# QR_Scanning2_V1_STM32.net
KiCad netlist of a schematic drawn in Altium Designer
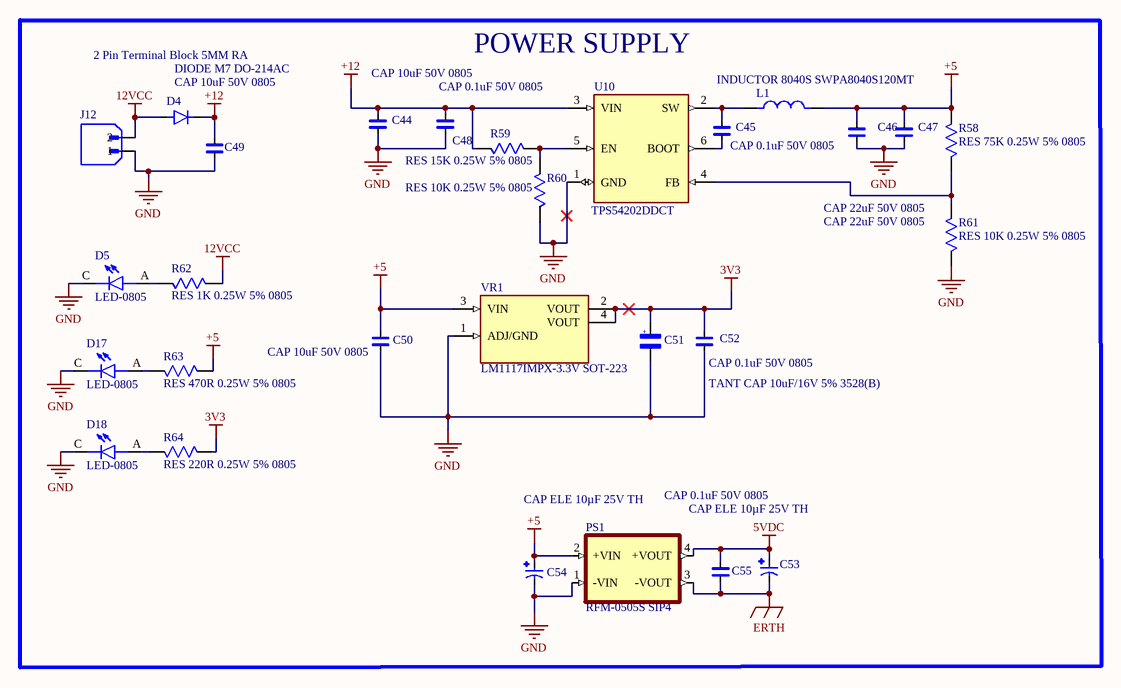
[diagram p0: QR_Scanning2_V1_STM32.SchDoc]

(export (version "E")
  (design (tool "Eeschema 10.0.6"))
  (components
    (comp (ref "C44")
      (value "CAP 10uF 50V 0805")
      (footprint "CAP CER 0.1uF/50V 5%")
      (description "CAP CER 0.1uF/50V  Ceramic Capacitor X7R 0805 (2012 Metric) SMT")
      (fields (field (name "MF") "Samsung") (field (name "MP") "CL21B104KCFNNNE"))
      (libsource (lib "GENERAL_ARDUINO+ESP32_PCB") (part "CAP CER 0.1uF/50V 5%"))
    )
    (comp (ref "C45")
      (value "CAP 0.1uF 50V 0805")
      (footprint "CAP CER 0.1uF/50V 5%")
      (description "CAP CER 0.1uF/50V  Ceramic Capacitor X7R 0805 (2012 Metric) SMT")
      (fields (field (name "MF") "Samsung") (field (name "MP") "CL21B104KCFNNNE"))
      (libsource (lib "GENERAL_ARDUINO+ESP32_PCB") (part "CAP CER 0.1uF/50V 5%"))
    )
    (comp (ref "C46")
      (value "CAP 22uF 50V 0805")
      (footprint "CAP CER 0.1uF/50V 5%")
      (description "CAP CER 0.1uF/50V  Ceramic Capacitor X7R 0805 (2012 Metric) SMT")
      (fields (field (name "MF") "Samsung") (field (name "MP") "CL21B104KCFNNNE"))
      (libsource (lib "GENERAL_ARDUINO+ESP32_PCB") (part "CAP CER 0.1uF/50V 5%"))
    )
    (comp (ref "C47")
      (value "CAP 22uF 50V 0805")
      (footprint "CAP CER 0.1uF/50V 5%")
      (description "CAP CER 0.1uF/50V  Ceramic Capacitor X7R 0805 (2012 Metric) SMT")
      (fields (field (name "MF") "Samsung") (field (name "MP") "CL21B104KCFNNNE"))
      (libsource (lib "GENERAL_ARDUINO+ESP32_PCB") (part "CAP CER 0.1uF/50V 5%"))
    )
    (comp (ref "C48")
      (value "CAP 0.1uF 50V 0805")
      (footprint "CAP CER 0.1uF/50V 5%")
      (description "CAP CER 0.1uF/50V  Ceramic Capacitor X7R 0805 (2012 Metric) SMT")
      (fields (field (name "MF") "Samsung") (field (name "MP") "CL21B104KCFNNNE"))
      (libsource (lib "GENERAL_ARDUINO+ESP32_PCB") (part "CAP CER 0.1uF/50V 5%"))
    )
    (comp (ref "C49")
      (value "CAP 10uF 50V 0805")
      (footprint "CAP CER 0.1uF/50V 5%")
      (description "CAP CER 0.1uF/50V  Ceramic Capacitor X7R 0805 (2012 Metric) SMT")
      (fields (field (name "MF") "Samsung") (field (name "MP") "CL21B104KCFNNNE"))
      (libsource (lib "Ticket Scanning") (part "CAP CER 0.1uF/50V 5%"))
    )
    (comp (ref "C50")
      (value "CAP 10uF 50V 0805")
      (footprint "CAP CER 0.1uF/50V 5%")
      (description "CAP CER 0.1uF/50V  Ceramic Capacitor X7R 0805 (2012 Metric) SMT")
      (fields (field (name "MF") "Samsung") (field (name "MP") "CL21B104KCFNNNE"))
      (libsource (lib "Ticket Scanning") (part "CAP CER 0.1uF/50V 5%"))
    )
    (comp (ref "C51")
      (value "TANT CAP 10uF/16V 5% 3528(B)")
      (footprint "TANT CAP 3528(B)")
      (description "10 ÂµF Molded Tantalum Polymer Capacitor 25 V 1411 (3528 Metric), 1210 150mOhm TCJB106M025R0150")
      (fields (field (name "MF") "AVX") (field (name "MP") "TCJB106M025R0150"))
      (libsource (lib "Ticket Scanning") (part "TANT CAP 10uF/16V 5% 3528(B)"))
    )
    (comp (ref "C52")
      (value "CAP 0.1uF 50V 0805")
      (footprint "CAP CER 0.1uF/50V 5%")
      (description "CAP CER 0.1uF/50V  Ceramic Capacitor X7R 0805 (2012 Metric) SMT")
      (fields (field (name "MF") "Samsung") (field (name "MP") "CL21B104KCFNNNE"))
      (libsource (lib "Ticket Scanning") (part "CAP CER 0.1uF/50V 5%"))
    )
    (comp (ref "C53")
      (value "CAP ELE 10µF 25V TH")
      (footprint "CAP ELE 10µF 25V TH")
      (description "10µF 25V Aluminum Electrolytic Capacitors Radial Lead Type TH, Dia-5mm, Pitch-2mm ECEA1EN100UI")
      (fields (field (name "MF") "Panasonic") (field (name "DIGI-KEY_PART_NUMBER") "ECE-A1EN100UI-ND"))
      (libsource (lib "PGS") (part "CAP ELE 10µF 25V TH"))
    )
    (comp (ref "C54")
      (value "CAP ELE 10µF 25V TH")
      (footprint "CAP ELE 10µF 25V TH")
      (description "10µF 25V Aluminum Electrolytic Capacitors Radial Lead Type TH, Dia-5mm, Pitch-2mm ECEA1EN100UI")
      (fields (field (name "MF") "Panasonic") (field (name "DIGI-KEY_PART_NUMBER") "ECE-A1EN100UI-ND"))
      (libsource (lib "PGS") (part "CAP ELE 10µF 25V TH"))
    )
    (comp (ref "C55")
      (value "CAP 0.1uF 50V 0805")
      (footprint "CAP CER 0.1uF/50V 5%")
      (description "CAP CER 0.1uF/50V  Ceramic Capacitor X7R 0805 (2012 Metric)")
      (fields (field (name "MF") "Samsung") (field (name "MP") "CL21B104KCFNNNE"))
      (libsource (lib "PGS") (part "CAP CER 0.1uF/50V 5%"))
    )
    (comp (ref "D4")
      (value "DIODE M7 DO-214AC")
      (footprint "DIODE M7 DO-214AC")
      (description "M7 General Purpose SMD Rectifier Diode SMA (DO-214AC) 1A 1000V 1n4007 RS2MA")
      (fields (field (name "MF") "Taiwan Semiconductor") (field (name "MP") "RS2MA"))
      (libsource (lib "QR_Scanning_STM32") (part "DIODE M7 DO-214AC"))
    )
    (comp (ref "D5")
      (value "LED-0805")
      (footprint "LED-0805")
      (description "Red 640nm LED Indication - Discrete 1.85V 0805 (2012 Metric) APT2012SRCPRV")
      (fields (field (name "MF") "Kingbright") (field (name "MP") "APT2012SRCPRV"))
      (libsource (lib "P10_ESP32") (part "LED-0805"))
    )
    (comp (ref "D17")
      (value "LED-0805")
      (footprint "LED-0805")
      (description "Red 640nm LED Indication - Discrete 1.85V 0805 (2012 Metric) APT2012SRCPRV")
      (fields (field (name "MF") "Kingbright") (field (name "MP") "APT2012SRCPRV"))
      (libsource (lib "P10_ESP32") (part "LED-0805"))
    )
    (comp (ref "D18")
      (value "LED-0805")
      (footprint "LED-0805")
      (description "Red 640nm LED Indication - Discrete 1.85V 0805 (2012 Metric) APT2012SRCPRV")
      (fields (field (name "MF") "Kingbright") (field (name "MP") "APT2012SRCPRV"))
      (libsource (lib "P10_ESP32") (part "LED-0805"))
    )
    (comp (ref "J12")
      (value "2 Pin Terminal Block 5MM RA")
      (footprint "2 Pin Terminal Block 5MM RA")
      (description "2 Pin Terminal Block HDR 5MM THT RA _OQ0271510000G")
      (fields (field (name "MF") "Amphenol Anytek") (field (name "MP") "OQ0271510000G"))
      (libsource (lib "Ticket Scanning") (part "2 Pin Terminal Block 5MM RA"))
    )
    (comp (ref "L1")
      (value "INDUCTOR 8040S SWPA8040S120MT")
      (footprint "INDUCTOR 8040S SWPA8040S120MT")
      (description "SWPA8040S120MT SMD 8.0×8.0x4.0mm 8040S 12uH Â±20% 2.8A 142 mOhm SMT Shielded Wirewound Inductor")
      (fields (field (name "MF") "Abracon LLC") (field (name "MP") "ASPI-8040S-510M-T"))
      (libsource (lib "QR_Scanning_STM32") (part "INDUCTOR 8040S SWPA8040S120MT"))
    )
    (comp (ref "PS1")
      (value "RFM-0505S SIP4")
      (footprint "RFM-0505S")
      (fields (field (name "MF") "Recom Power") (field (name "MP") "RFM-0505S"))
      (libsource (lib "PGS") (part "RFM-0505S"))
    )
    (comp (ref "R58")
      (value "RES 75K 0.25W 5% 0805")
      (footprint "RES 0805 10K/0.25W 5%")
      (description "RESISTOR, THICK FILM, 10K, 5%, 0805 0.25W SMT")
      (fields (field (name "MP") "ERJ-6GEYJ103V") (field (name "MF") "Panasonic Electronic"))
      (libsource (lib "GENERAL_ARDUINO+ESP32_PCB") (part "RES 10K 0.25W 5% 0805"))
    )
    (comp (ref "R59")
      (value "RES 15K 0.25W 5% 0805")
      (footprint "RES 0805 10K/0.25W 5%")
      (description "RESISTOR, THICK FILM, 10K, 5%, 0805 0.25W SMT")
      (fields (field (name "MP") "ERJ-6GEYJ103V") (field (name "MF") "Panasonic Electronic"))
      (libsource (lib "GENERAL_ARDUINO+ESP32_PCB") (part "RES 10K 0.25W 5% 0805"))
    )
    (comp (ref "R60")
      (value "RES 10K 0.25W 5% 0805")
      (footprint "RES 0805 10K/0.25W 5%")
      (description "RESISTOR, THICK FILM, 10K, 5%, 0805 0.25W SMT")
      (fields (field (name "MP") "ERJ-6GEYJ103V") (field (name "MF") "Panasonic Electronic"))
      (libsource (lib "GENERAL_ARDUINO+ESP32_PCB") (part "RES 10K 0.25W 5% 0805"))
    )
    (comp (ref "R61")
      (value "RES 10K 0.25W 5% 0805")
      (footprint "RES 0805 10K/0.25W 5%")
      (description "RESISTOR, THICK FILM, 10K, 5%, 0805 0.25W SMT")
      (fields (field (name "MP") "ERJ-6GEYJ103V") (field (name "MF") "Panasonic Electronic"))
      (libsource (lib "GENERAL_ARDUINO+ESP32_PCB") (part "RES 10K 0.25W 5% 0805"))
    )
    (comp (ref "R62")
      (value "RES 1K 0.25W 5% 0805")
      (footprint "RES 0805 10K/0.25W 5%")
      (description "RESISTOR, THICK FILM, 10K, 5%, 0805 0.25W SMT")
      (fields (field (name "MP") "ERJ-6GEYJ103V") (field (name "MF") "Panasonic Electronic"))
      (libsource (lib "Ticket Scanning") (part "RES 10K 0.25W 5% 0805"))
    )
    (comp (ref "R63")
      (value "RES 470R 0.25W 5% 0805")
      (footprint "RES 0805 10K/0.25W 5%")
      (description "RESISTOR, THICK FILM, 10K, 5%, 0805 0.25W SMT")
      (fields (field (name "MP") "ERJ-6GEYJ103V") (field (name "MF") "Panasonic Electronic"))
      (libsource (lib "Ticket Scanning") (part "RES 10K 0.25W 5% 0805"))
    )
    (comp (ref "R64")
      (value "RES 220R 0.25W 5% 0805")
      (footprint "RES 0805 10K/0.25W 5%")
      (description "RESISTOR, THICK FILM, 10K, 5%, 0805 0.25W SMT")
      (fields (field (name "MP") "ERJ-6GEYJ103V") (field (name "MF") "Panasonic Electronic"))
      (libsource (lib "Ticket Scanning") (part "RES 10K 0.25W 5% 0805"))
    )
    (comp (ref "U10")
      (value "TPS54202DDCT")
      (footprint "TPS54202DDCT")
      (description "4.5V to 28V Input, 2A Output, EMI Friendly Synchronous Step-Down Converter SOT23-6")
      (fields (field (name "MF") "Texas Instruments"))
      (libsource (lib "GENERAL_ARDUINO+ESP32_PCB") (part "TPS54202DDCT"))
    )
    (comp (ref "VR1")
      (value "LM1117IMPX-3.3V SOT-223")
      (footprint "LM1117IMPX-3.3V SOT-223")
      (description "LM1117IMPX-3.3V 800-mA 15-V linear voltage regulator SOT-223")
      (fields (field (name "MF") "Texas Instruments") (field (name "MP") "LM1117IMPX-5.0/NOPB"))
      (libsource (lib "Ticket Scanning") (part "LM1117IMPX-3.3V SOT-223"))
    )
  )
  (nets
    (net (code "1") (name "+5") (class "Default")
      (node (ref "C46") (pin "2") (pinfunction "2_2") (pintype "passive"))
      (node (ref "C47") (pin "2") (pinfunction "2_2") (pintype "passive"))
      (node (ref "C50") (pin "2") (pinfunction "2_2") (pintype "passive"))
      (node (ref "C54") (pin "P") (pinfunction "P_P") (pintype "passive"))
      (node (ref "L1") (pin "2") (pinfunction "2_2") (pintype "passive"))
      (node (ref "PS1") (pin "2") (pinfunction "+VIN_2") (pintype "input"))
      (node (ref "R58") (pin "2") (pinfunction "2_2") (pintype "passive"))
      (node (ref "R63") (pin "2") (pinfunction "2_2") (pintype "passive"))
      (node (ref "VR1") (pin "3") (pinfunction "VIN_3") (pintype "input"))
    )
    (net (code "2") (name "+12") (class "Default")
      (node (ref "C44") (pin "2") (pinfunction "2_2") (pintype "passive"))
      (node (ref "C48") (pin "2") (pinfunction "2_2") (pintype "passive"))
      (node (ref "C49") (pin "2") (pinfunction "2_2") (pintype "passive"))
      (node (ref "D4") (pin "C") (pinfunction "K_C") (pintype "passive"))
      (node (ref "R59") (pin "1") (pinfunction "1_1") (pintype "passive"))
      (node (ref "U10") (pin "3") (pinfunction "VIN_3") (pintype "input"))
    )
    (net (code "3") (name "3V3") (class "Default")
      (node (ref "C51") (pin "1") (pinfunction "1_1") (pintype "passive"))
      (node (ref "C52") (pin "2") (pinfunction "2_2") (pintype "passive"))
      (node (ref "R64") (pin "2") (pinfunction "2_2") (pintype "passive"))
      (node (ref "VR1") (pin "2") (pinfunction "VOUT_2") (pintype "power_in"))
      (node (ref "VR1") (pin "4") (pinfunction "VOUT_4") (pintype "power_in"))
    )
    (net (code "4") (name "5VDC") (class "Default")
      (node (ref "C53") (pin "P") (pinfunction "P_P") (pintype "passive"))
      (node (ref "C55") (pin "2") (pinfunction "2_2") (pintype "passive"))
      (node (ref "PS1") (pin "4") (pinfunction "+VOUT_4") (pintype "output"))
    )
    (net (code "5") (name "12VCC") (class "Default")
      (node (ref "D4") (pin "A") (pinfunction "A_A") (pintype "passive"))
      (node (ref "J12") (pin "2") (pinfunction "2_2") (pintype "passive"))
      (node (ref "R62") (pin "2") (pinfunction "2_2") (pintype "passive"))
    )
    (net (code "6") (name "ERTH") (class "Default")
      (node (ref "C53") (pin "N") (pinfunction "N_N") (pintype "passive"))
      (node (ref "C55") (pin "1") (pinfunction "1_1") (pintype "passive"))
      (node (ref "PS1") (pin "3") (pinfunction "-VOUT_3") (pintype "output"))
    )
    (net (code "7") (name "GND") (class "Default")
      (node (ref "C44") (pin "1") (pinfunction "1_1") (pintype "passive"))
      (node (ref "C46") (pin "1") (pinfunction "1_1") (pintype "passive"))
      (node (ref "C47") (pin "1") (pinfunction "1_1") (pintype "passive"))
      (node (ref "C48") (pin "1") (pinfunction "1_1") (pintype "passive"))
      (node (ref "C49") (pin "1") (pinfunction "1_1") (pintype "passive"))
      (node (ref "C50") (pin "1") (pinfunction "1_1") (pintype "passive"))
      (node (ref "C51") (pin "2") (pinfunction "2_2") (pintype "passive"))
      (node (ref "C52") (pin "1") (pinfunction "1_1") (pintype "passive"))
      (node (ref "C54") (pin "N") (pinfunction "N_N") (pintype "passive"))
      (node (ref "D17") (pin "C") (pinfunction "C_C") (pintype "passive"))
      (node (ref "D18") (pin "C") (pinfunction "C_C") (pintype "passive"))
      (node (ref "D5") (pin "C") (pinfunction "C_C") (pintype "passive"))
      (node (ref "J12") (pin "1") (pinfunction "1_1") (pintype "passive"))
      (node (ref "PS1") (pin "1") (pinfunction "-VIN_1") (pintype "input"))
      (node (ref "R60") (pin "1") (pinfunction "1_1") (pintype "passive"))
      (node (ref "R61") (pin "1") (pinfunction "1_1") (pintype "passive"))
      (node (ref "U10") (pin "1") (pinfunction "GND_1") (pintype "bidirectional"))
      (node (ref "VR1") (pin "1") (pinfunction "ADJ/GND_1") (pintype "input"))
    )
    (net (code "8") (name "Net-(D5-PadA)") (class "Default")
      (node (ref "D5") (pin "A") (pinfunction "A_A") (pintype "passive"))
      (node (ref "R62") (pin "1") (pinfunction "1_1") (pintype "passive"))
    )
    (net (code "9") (name "Net-(D17-PadA)") (class "Default")
      (node (ref "D17") (pin "A") (pinfunction "A_A") (pintype "passive"))
      (node (ref "R63") (pin "1") (pinfunction "1_1") (pintype "passive"))
    )
    (net (code "10") (name "Net-(D18-PadA)") (class "Default")
      (node (ref "D18") (pin "A") (pinfunction "A_A") (pintype "passive"))
      (node (ref "R64") (pin "1") (pinfunction "1_1") (pintype "passive"))
    )
    (net (code "11") (name "Net-(U10-BOOT)") (class "Default")
      (node (ref "C45") (pin "1") (pinfunction "1_1") (pintype "passive"))
      (node (ref "U10") (pin "6") (pinfunction "BOOT_6") (pintype "output"))
    )
    (net (code "12") (name "Net-(U10-EN)") (class "Default")
      (node (ref "R59") (pin "2") (pinfunction "2_2") (pintype "passive"))
      (node (ref "R60") (pin "2") (pinfunction "2_2") (pintype "passive"))
      (node (ref "U10") (pin "5") (pinfunction "EN_5") (pintype "input"))
    )
    (net (code "13") (name "Net-(U10-FB)") (class "Default")
      (node (ref "R58") (pin "1") (pinfunction "1_1") (pintype "passive"))
      (node (ref "R61") (pin "2") (pinfunction "2_2") (pintype "passive"))
      (node (ref "U10") (pin "4") (pinfunction "FB_4") (pintype "input"))
    )
    (net (code "14") (name "Net-(U10-SW)") (class "Default")
      (node (ref "C45") (pin "2") (pinfunction "2_2") (pintype "passive"))
      (node (ref "L1") (pin "1") (pinfunction "1_1") (pintype "passive"))
      (node (ref "U10") (pin "2") (pinfunction "SW_2") (pintype "output"))
    )
  )
)
